# SCH_usb-hub_2024-05-01.net
KiCad netlist of a schematic drawn in EasyEDA
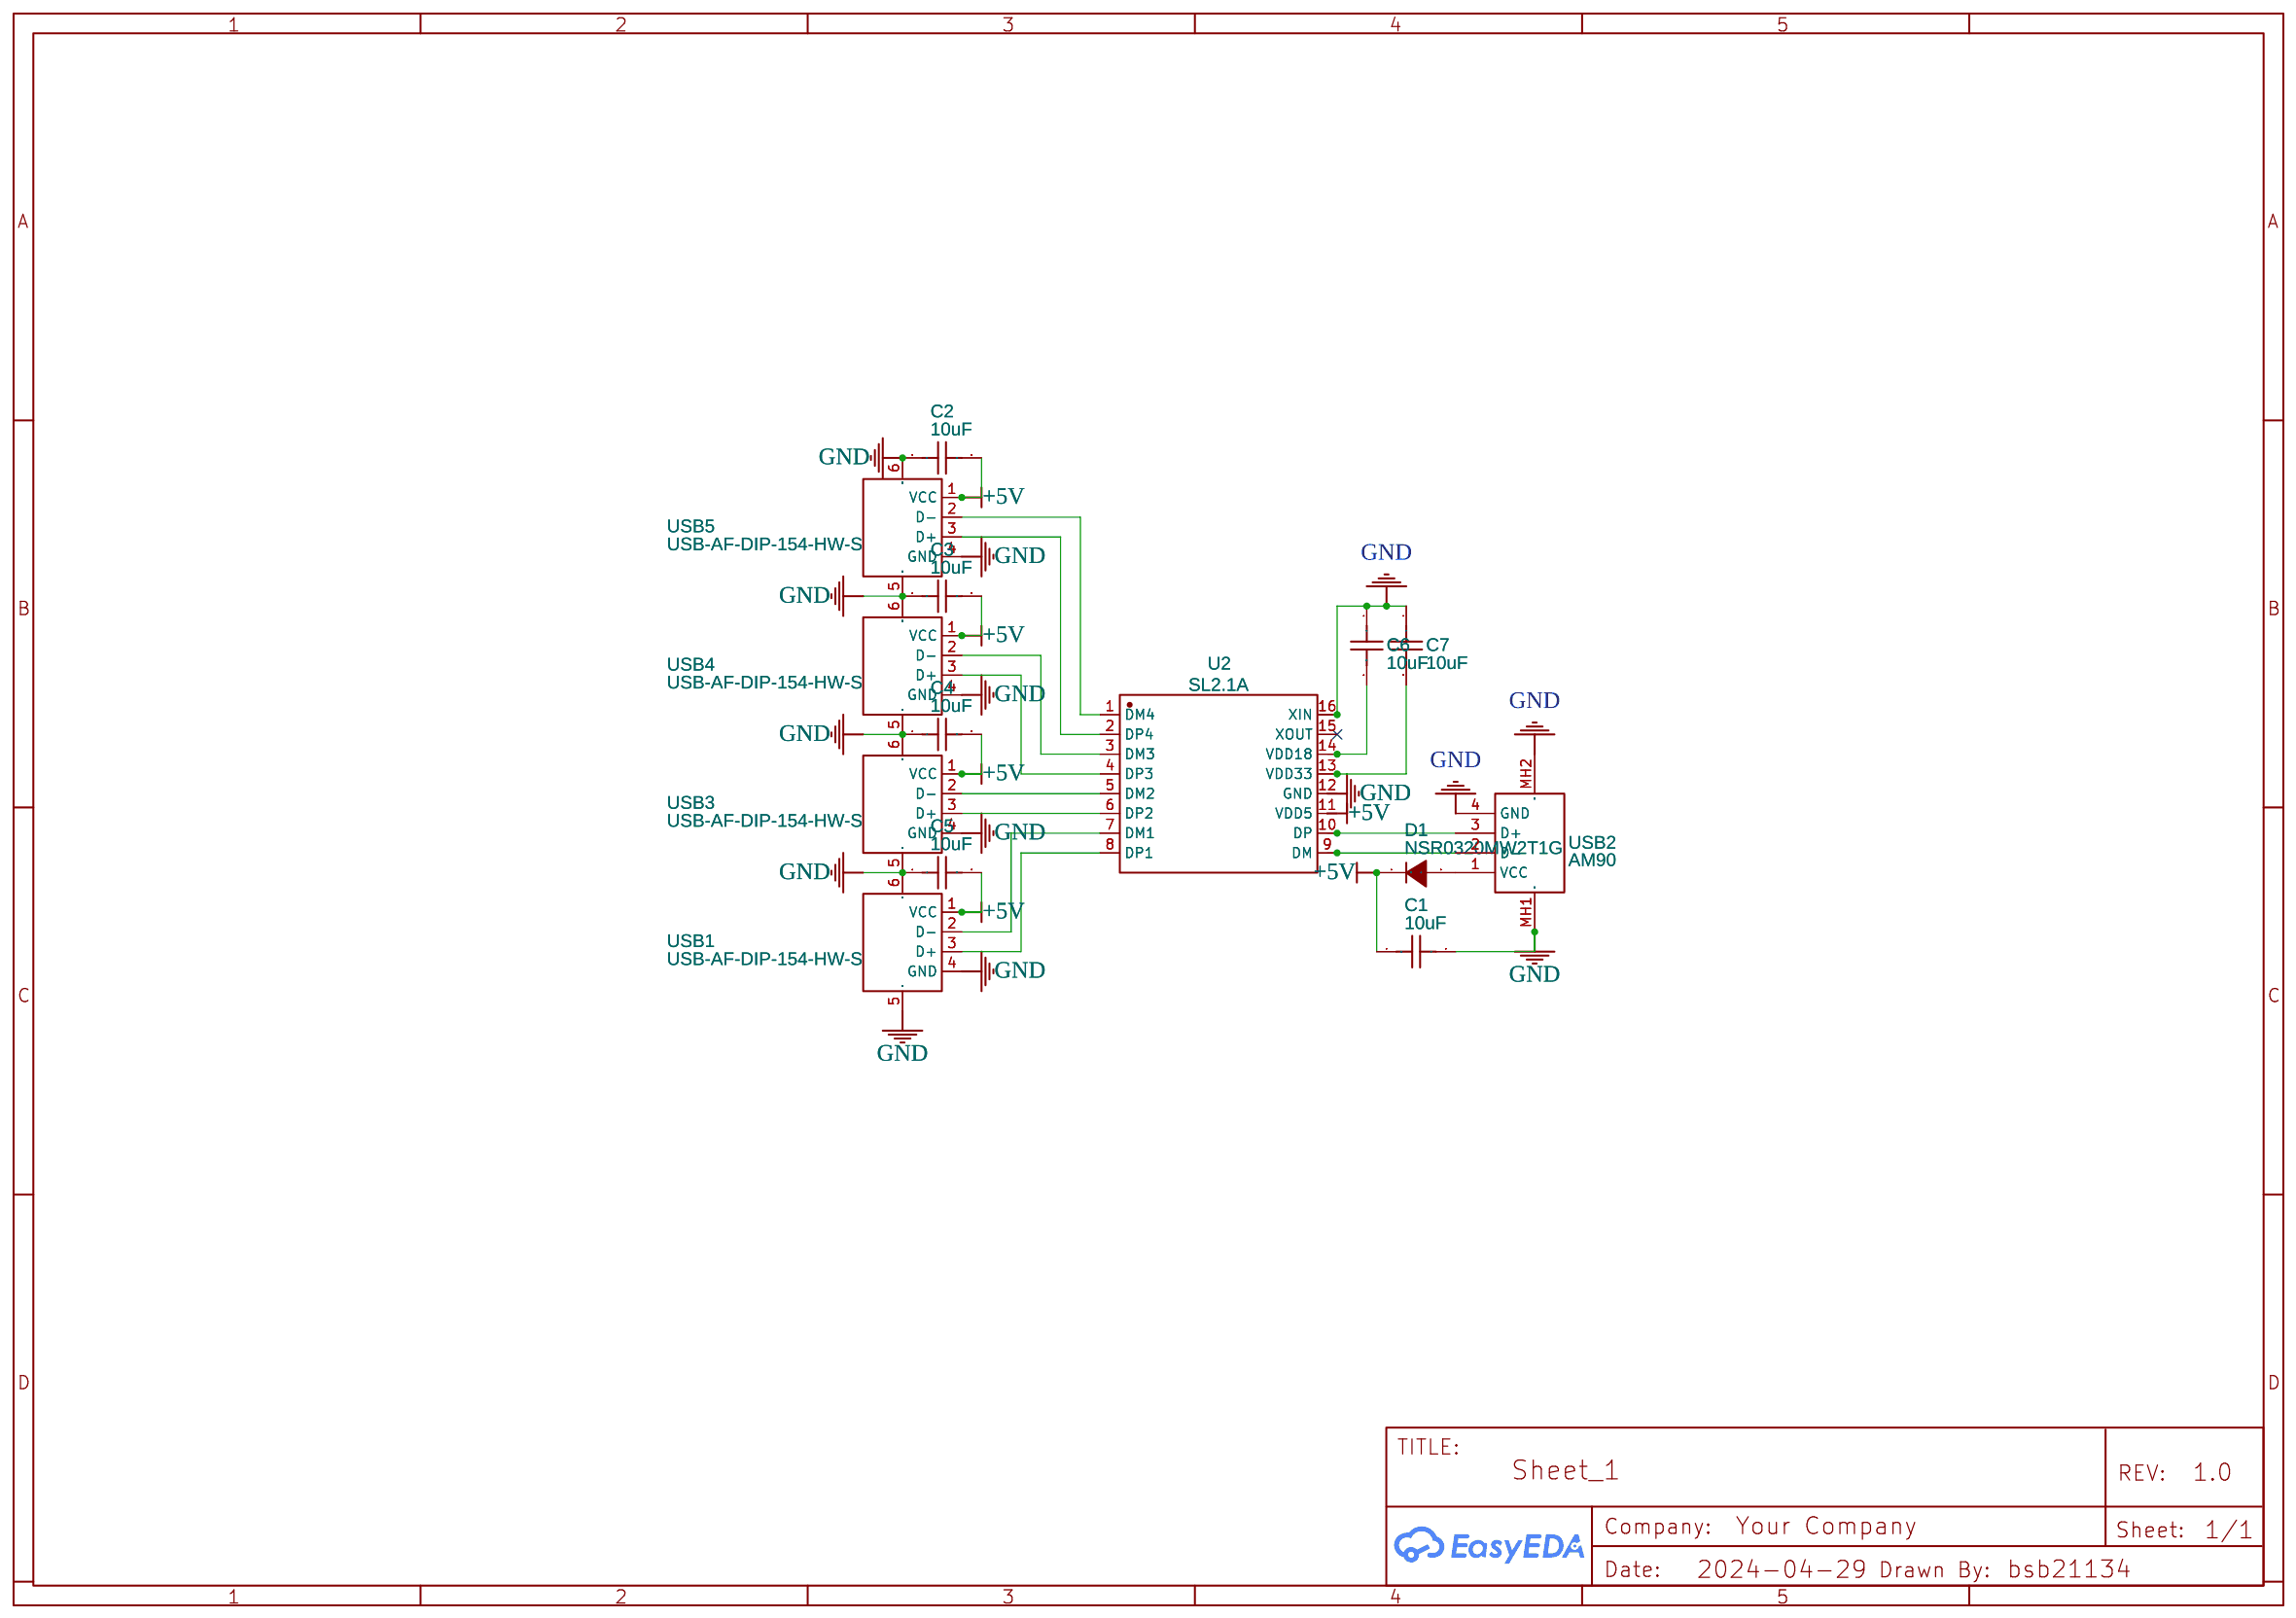
[diagram p0: schematic sheet]

(export (version "E")
  (design (tool "Eeschema 10.0.6"))
  (components
    (comp (ref "C1")
      (value "10uF")
      (fields
        (field (name "Manufacturer Part") "CL10A106KP8NNNC")
        (field (name "Manufacturer") "SAMSUNG(三星)")
      )
      (libsource (lib "") (part "CL10A106KP8NNNC"))
    )
    (comp (ref "C2")
      (value "10uF")
      (fields
        (field (name "Manufacturer Part") "CL10A106KP8NNNC")
        (field (name "Manufacturer") "SAMSUNG(三星)")
      )
      (libsource (lib "") (part "CL10A106KP8NNNC"))
    )
    (comp (ref "C3")
      (value "10uF")
      (fields
        (field (name "Manufacturer Part") "CL10A106KP8NNNC")
        (field (name "Manufacturer") "SAMSUNG(三星)")
      )
      (libsource (lib "") (part "CL10A106KP8NNNC"))
    )
    (comp (ref "C4")
      (value "10uF")
      (fields
        (field (name "Manufacturer Part") "CL10A106KP8NNNC")
        (field (name "Manufacturer") "SAMSUNG(三星)")
      )
      (libsource (lib "") (part "CL10A106KP8NNNC"))
    )
    (comp (ref "C5")
      (value "10uF")
      (fields
        (field (name "Manufacturer Part") "CL10A106KP8NNNC")
        (field (name "Manufacturer") "SAMSUNG(三星)")
      )
      (libsource (lib "") (part "CL10A106KP8NNNC"))
    )
    (comp (ref "C6")
      (value "10uF")
      (fields
        (field (name "Manufacturer Part") "CL10A106KP8NNNC")
        (field (name "Manufacturer") "SAMSUNG(三星)")
      )
      (libsource (lib "") (part "CL10A106KP8NNNC_1"))
    )
    (comp (ref "C7")
      (value "10uF")
      (fields
        (field (name "Manufacturer Part") "CL10A106KP8NNNC")
        (field (name "Manufacturer") "SAMSUNG(三星)")
      )
      (libsource (lib "") (part "CL10A106KP8NNNC_1"))
    )
    (comp (ref "D1")
      (value "NSR0320MW2T1G")
      (fields (field (name "Manufacturer") "onsemi(安森美)"))
      (libsource (lib "") (part "NSR0320MW2T1G"))
    )
    (comp (ref "U2")
      (value "SL2.1A")
      (fields (field (name "Manufacturer") "CoreChips(和芯润德)"))
      (libsource (lib "") (part "SL2.1A"))
    )
    (comp (ref "USB1")
      (value "USB-AF-DIP-154-HW-S")
      (fields (field (name "Manufacturer") "皇捷"))
      (libsource (lib "") (part "USB-AF-DIP-154-HW-S"))
    )
    (comp (ref "USB2")
      (value "AM90")
      (fields (field (name "Manufacturer") "SHOU HAN(首韩)"))
      (libsource (lib "") (part "AM90"))
    )
    (comp (ref "USB3")
      (value "USB-AF-DIP-154-HW-S")
      (fields (field (name "Manufacturer") "皇捷"))
      (libsource (lib "") (part "USB-AF-DIP-154-HW-S"))
    )
    (comp (ref "USB4")
      (value "USB-AF-DIP-154-HW-S")
      (fields (field (name "Manufacturer") "皇捷"))
      (libsource (lib "") (part "USB-AF-DIP-154-HW-S"))
    )
    (comp (ref "USB5")
      (value "USB-AF-DIP-154-HW-S")
      (fields (field (name "Manufacturer") "皇捷"))
      (libsource (lib "") (part "USB-AF-DIP-154-HW-S"))
    )
  )
  (nets
    (net (code "1") (name "+5V") (class "Default")
      (node (ref "C1") (pin "1") (pinfunction "1_1") (pintype "unspecified"))
      (node (ref "C2") (pin "2") (pinfunction "2_2") (pintype "unspecified"))
      (node (ref "C3") (pin "2") (pinfunction "2_2") (pintype "unspecified"))
      (node (ref "C4") (pin "2") (pinfunction "2_2") (pintype "unspecified"))
      (node (ref "C5") (pin "2") (pinfunction "2_2") (pintype "unspecified"))
      (node (ref "D1") (pin "1") (pinfunction "C_1") (pintype "unspecified"))
      (node (ref "U2") (pin "11") (pinfunction "VDD5_11") (pintype "unspecified"))
      (node (ref "USB1") (pin "1") (pinfunction "VCC_1") (pintype "input"))
      (node (ref "USB3") (pin "1") (pinfunction "VCC_1") (pintype "input"))
      (node (ref "USB4") (pin "1") (pinfunction "VCC_1") (pintype "input"))
      (node (ref "USB5") (pin "1") (pinfunction "VCC_1") (pintype "input"))
    )
    (net (code "2") (name "GND") (class "Default")
      (node (ref "C1") (pin "2") (pinfunction "2_2") (pintype "unspecified"))
      (node (ref "C2") (pin "1") (pinfunction "1_1") (pintype "unspecified"))
      (node (ref "C3") (pin "1") (pinfunction "1_1") (pintype "unspecified"))
      (node (ref "C4") (pin "1") (pinfunction "1_1") (pintype "unspecified"))
      (node (ref "C5") (pin "1") (pinfunction "1_1") (pintype "unspecified"))
      (node (ref "C6") (pin "1") (pinfunction "1_1") (pintype "unspecified"))
      (node (ref "C7") (pin "1") (pinfunction "1_1") (pintype "unspecified"))
      (node (ref "U2") (pin "12") (pinfunction "GND_12") (pintype "unspecified"))
      (node (ref "U2") (pin "16") (pinfunction "XIN_16") (pintype "unspecified"))
      (node (ref "USB1") (pin "4") (pinfunction "GND_4") (pintype "input"))
      (node (ref "USB1") (pin "5") (pinfunction "SH1_5") (pintype "unspecified"))
      (node (ref "USB1") (pin "6") (pinfunction "SH2_6") (pintype "unspecified"))
      (node (ref "USB2") (pin "4") (pinfunction "GND_4") (pintype "input"))
      (node (ref "USB2") (pin "MH1") (pinfunction "MH1_MH1") (pintype "unspecified"))
      (node (ref "USB2") (pin "MH2") (pinfunction "MH2_MH2") (pintype "unspecified"))
      (node (ref "USB3") (pin "4") (pinfunction "GND_4") (pintype "input"))
      (node (ref "USB3") (pin "5") (pinfunction "SH1_5") (pintype "unspecified"))
      (node (ref "USB3") (pin "6") (pinfunction "SH2_6") (pintype "unspecified"))
      (node (ref "USB4") (pin "4") (pinfunction "GND_4") (pintype "input"))
      (node (ref "USB4") (pin "5") (pinfunction "SH1_5") (pintype "unspecified"))
      (node (ref "USB4") (pin "6") (pinfunction "SH2_6") (pintype "unspecified"))
      (node (ref "USB5") (pin "4") (pinfunction "GND_4") (pintype "input"))
      (node (ref "USB5") (pin "5") (pinfunction "SH1_5") (pintype "unspecified"))
      (node (ref "USB5") (pin "6") (pinfunction "SH2_6") (pintype "unspecified"))
    )
    (net (code "3") (name "Net-(D1-A)") (class "Default")
      (node (ref "D1") (pin "2") (pinfunction "A_2") (pintype "unspecified"))
      (node (ref "USB2") (pin "1") (pinfunction "VCC_1") (pintype "input"))
    )
    (net (code "4") (name "Net-(U2-DM)") (class "Default")
      (node (ref "U2") (pin "9") (pinfunction "DM_9") (pintype "unspecified"))
      (node (ref "USB2") (pin "2") (pinfunction "D-_2") (pintype "input"))
    )
    (net (code "5") (name "Net-(U2-DM1)") (class "Default")
      (node (ref "U2") (pin "7") (pinfunction "DM1_7") (pintype "unspecified"))
      (node (ref "USB1") (pin "2") (pinfunction "D-_2") (pintype "input"))
    )
    (net (code "6") (name "Net-(U2-DM2)") (class "Default")
      (node (ref "U2") (pin "5") (pinfunction "DM2_5") (pintype "unspecified"))
      (node (ref "USB3") (pin "2") (pinfunction "D-_2") (pintype "input"))
    )
    (net (code "7") (name "Net-(U2-DM3)") (class "Default")
      (node (ref "U2") (pin "3") (pinfunction "DM3_3") (pintype "unspecified"))
      (node (ref "USB4") (pin "2") (pinfunction "D-_2") (pintype "input"))
    )
    (net (code "8") (name "Net-(U2-DM4)") (class "Default")
      (node (ref "U2") (pin "1") (pinfunction "DM4_1") (pintype "unspecified"))
      (node (ref "USB5") (pin "2") (pinfunction "D-_2") (pintype "input"))
    )
    (net (code "9") (name "Net-(U2-DP)") (class "Default")
      (node (ref "U2") (pin "10") (pinfunction "DP_10") (pintype "unspecified"))
      (node (ref "USB2") (pin "3") (pinfunction "D+_3") (pintype "input"))
    )
    (net (code "10") (name "Net-(U2-DP1)") (class "Default")
      (node (ref "U2") (pin "8") (pinfunction "DP1_8") (pintype "unspecified"))
      (node (ref "USB1") (pin "3") (pinfunction "D+_3") (pintype "input"))
    )
    (net (code "11") (name "Net-(U2-DP2)") (class "Default")
      (node (ref "U2") (pin "6") (pinfunction "DP2_6") (pintype "unspecified"))
      (node (ref "USB3") (pin "3") (pinfunction "D+_3") (pintype "input"))
    )
    (net (code "12") (name "Net-(U2-DP3)") (class "Default")
      (node (ref "U2") (pin "4") (pinfunction "DP3_4") (pintype "unspecified"))
      (node (ref "USB4") (pin "3") (pinfunction "D+_3") (pintype "input"))
    )
    (net (code "13") (name "Net-(U2-DP4)") (class "Default")
      (node (ref "U2") (pin "2") (pinfunction "DP4_2") (pintype "unspecified"))
      (node (ref "USB5") (pin "3") (pinfunction "D+_3") (pintype "input"))
    )
    (net (code "14") (name "Net-(U2-VDD18)") (class "Default")
      (node (ref "C6") (pin "2") (pinfunction "2_2") (pintype "unspecified"))
      (node (ref "U2") (pin "14") (pinfunction "VDD18_14") (pintype "unspecified"))
    )
    (net (code "15") (name "Net-(U2-VDD33)") (class "Default")
      (node (ref "C7") (pin "2") (pinfunction "2_2") (pintype "unspecified"))
      (node (ref "U2") (pin "13") (pinfunction "VDD33_13") (pintype "unspecified"))
    )
    (net (code "16") (name "unconnected-(U2-XOUT-Pad15)") (class "Default")
      (node (ref "U2") (pin "15") (pinfunction "XOUT_15") (pintype "unspecified+no_connect"))
    )
  )
)
